# SATCOM_LEVELSHIFTER.net
KiCad netlist of a schematic drawn in EAGLE
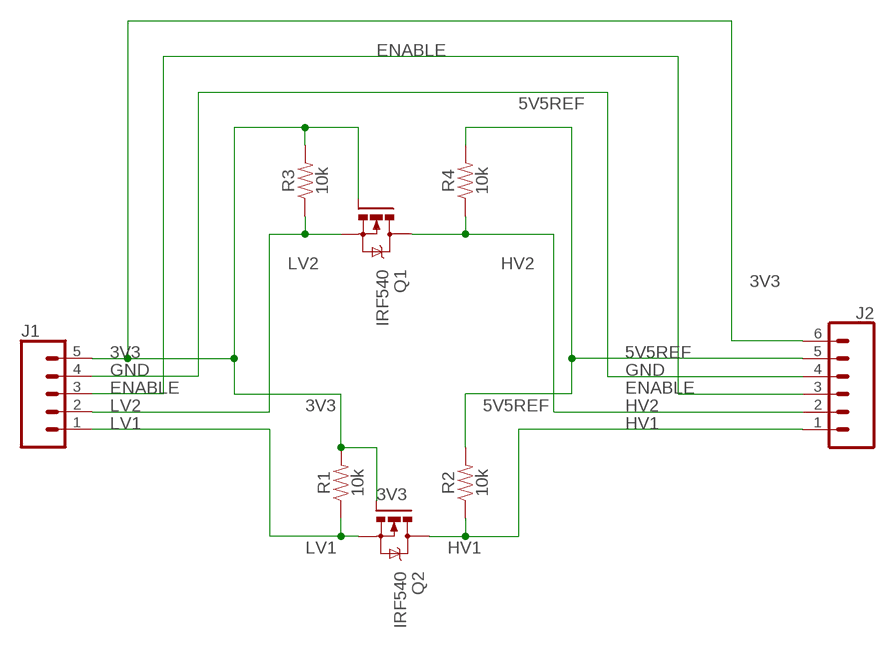
[diagram p0: schematic, sheet 1]

(export (version "E")
  (design (tool "Eeschema 10.0.6"))
  (components
    (comp (ref "J1")
      (value "CONN_05PTH_LONGPADS")
      (footprint "eagle-import:1X05_LONGPADS")
      (libsource (lib "eagle-import") (part "CONN_05PTH_LONGPADS"))
    )
    (comp (ref "J2")
      (value "CONN_06LONGPADS")
      (footprint "eagle-import:1X06_LONGPADS")
      (libsource (lib "eagle-import") (part "CONN_06LONGPADS"))
    )
    (comp (ref "Q1")
      (value "IRF540")
      (footprint "eagle-import:TO220BV")
      (libsource (lib "eagle-import") (part "IRF540"))
    )
    (comp (ref "Q2")
      (value "IRF540")
      (footprint "eagle-import:TO220BV")
      (libsource (lib "eagle-import") (part "IRF540"))
    )
    (comp (ref "R1")
      (value "10k")
      (footprint "eagle-import:AXIAL-0.3-KIT")
      (libsource (lib "eagle-import") (part "10KOHM-HORIZ_KIT-1/4W-1%"))
    )
    (comp (ref "R2")
      (value "10k")
      (footprint "eagle-import:AXIAL-0.3-KIT")
      (libsource (lib "eagle-import") (part "10KOHM-HORIZ_KIT-1/4W-1%"))
    )
    (comp (ref "R3")
      (value "10k")
      (footprint "eagle-import:AXIAL-0.3-KIT")
      (libsource (lib "eagle-import") (part "10KOHM-HORIZ_KIT-1/4W-1%"))
    )
    (comp (ref "R4")
      (value "10k")
      (footprint "eagle-import:AXIAL-0.3-KIT")
      (libsource (lib "eagle-import") (part "10KOHM-HORIZ_KIT-1/4W-1%"))
    )
  )
  (nets
    (net (code "1") (name "/3V3") (class "Default")
      (node (ref "J1") (pin "5") (pinfunction "5_5") (pintype "passive"))
      (node (ref "J2") (pin "6") (pinfunction "6_6") (pintype "passive"))
      (node (ref "Q1") (pin "G") (pinfunction "G_G") (pintype "passive"))
      (node (ref "Q2") (pin "G") (pinfunction "G_G") (pintype "passive"))
      (node (ref "R1") (pin "P$2") (pinfunction "2_P$2") (pintype "passive"))
      (node (ref "R3") (pin "P$2") (pinfunction "2_P$2") (pintype "passive"))
    )
    (net (code "2") (name "/5V5REF") (class "Default")
      (node (ref "J2") (pin "5") (pinfunction "5_5") (pintype "passive"))
      (node (ref "R2") (pin "P$2") (pinfunction "2_P$2") (pintype "passive"))
      (node (ref "R4") (pin "P$2") (pinfunction "2_P$2") (pintype "passive"))
    )
    (net (code "3") (name "/ENABLE") (class "Default")
      (node (ref "J1") (pin "3") (pinfunction "3_3") (pintype "passive"))
      (node (ref "J2") (pin "3") (pinfunction "3_3") (pintype "passive"))
    )
    (net (code "4") (name "/GND") (class "Default")
      (node (ref "J1") (pin "4") (pinfunction "4_4") (pintype "passive"))
      (node (ref "J2") (pin "4") (pinfunction "4_4") (pintype "passive"))
    )
    (net (code "5") (name "/HV1") (class "Default")
      (node (ref "J2") (pin "1") (pinfunction "1_1") (pintype "passive"))
      (node (ref "Q2") (pin "D") (pinfunction "D_D") (pintype "passive"))
      (node (ref "R2") (pin "P$1") (pinfunction "1_P$1") (pintype "passive"))
    )
    (net (code "6") (name "/HV2") (class "Default")
      (node (ref "J2") (pin "2") (pinfunction "2_2") (pintype "passive"))
      (node (ref "Q1") (pin "D") (pinfunction "D_D") (pintype "passive"))
      (node (ref "R4") (pin "P$1") (pinfunction "1_P$1") (pintype "passive"))
    )
    (net (code "7") (name "/LV1") (class "Default")
      (node (ref "J1") (pin "1") (pinfunction "1_1") (pintype "passive"))
      (node (ref "Q2") (pin "S") (pinfunction "S_S") (pintype "passive"))
      (node (ref "R1") (pin "P$1") (pinfunction "1_P$1") (pintype "passive"))
    )
    (net (code "8") (name "/LV2") (class "Default")
      (node (ref "J1") (pin "2") (pinfunction "2_2") (pintype "passive"))
      (node (ref "Q1") (pin "S") (pinfunction "S_S") (pintype "passive"))
      (node (ref "R3") (pin "P$1") (pinfunction "1_P$1") (pintype "passive"))
    )
  )
)
